# untitled_2.net
KiCad netlist of a schematic drawn in EAGLE
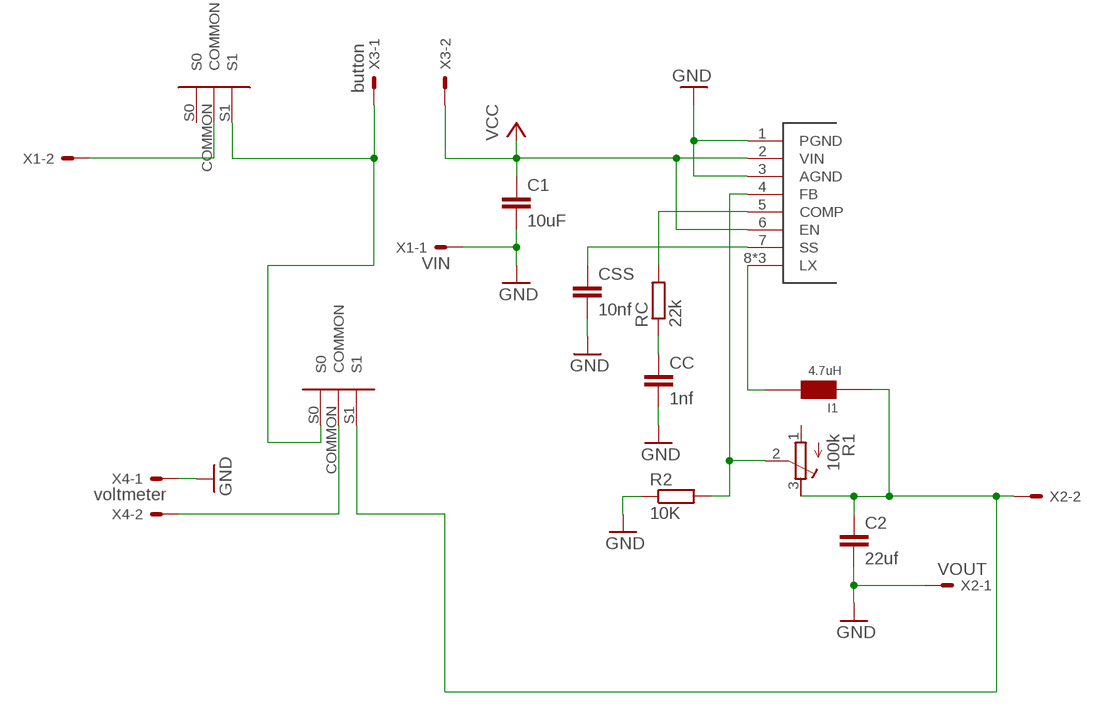
[diagram p0: schematic, sheet 1]

(export (version "E")
  (design (tool "Eeschema 10.0.6"))
  (components
    (comp (ref "C1")
      (value "10uF")
      (footprint "eagle-import:C0805K")
      (libsource (lib "eagle-import") (part "C-EUC0805K"))
    )
    (comp (ref "C2")
      (value "22uf")
      (footprint "eagle-import:C0805K")
      (libsource (lib "eagle-import") (part "C-EUC0805K"))
    )
    (comp (ref "CC")
      (value "1nf")
      (footprint "eagle-import:C1206K")
      (libsource (lib "eagle-import") (part "C-EUC1206K"))
    )
    (comp (ref "CSS")
      (value "10nf")
      (footprint "eagle-import:C1206K")
      (libsource (lib "eagle-import") (part "C-EUC1206K"))
    )
    (comp (ref "I1")
      (value "4.7uH")
      (footprint "eagle-import:RH127")
      (libsource (lib "eagle-import") (part "RH127"))
    )
    (comp (ref "MASTER_ON")
      (value "SPDT_SLIDE_SWITCH_2_PITCH")
      (footprint "eagle-import:SPDT_SLIDE_SWITCH_2_PITCH")
      (libsource (lib "eagle-import") (part "SPDT_SLIDE_SWITCH_2_PITCH"))
    )
    (comp (ref "METER_SWITCH")
      (value "SPDT_SLIDE_SWITCH_2_PITCH")
      (footprint "eagle-import:SPDT_SLIDE_SWITCH_2_PITCH")
      (libsource (lib "eagle-import") (part "SPDT_SLIDE_SWITCH_2_PITCH"))
    )
    (comp (ref "R1")
      (value "100k")
      (footprint "eagle-import:RTRIM64W")
      (libsource (lib "eagle-import") (part "R-TRIMM64W"))
    )
    (comp (ref "R2")
      (value "10K")
      (footprint "eagle-import:R1206")
      (libsource (lib "eagle-import") (part "R-EU_R1206"))
    )
    (comp (ref "RC")
      (value "22k")
      (footprint "eagle-import:R1206")
      (libsource (lib "eagle-import") (part "R-EU_R1206"))
    )
    (comp (ref "U$3")
      (value "AOZ1051PI")
      (footprint "eagle-import:AOZ1051PI")
      (libsource (lib "eagle-import") (part "AOZ1051PI"))
    )
    (comp (ref "X1")
      (value "VIN")
      (footprint "eagle-import:XH2.54")
      (fields (field (name "MF") "MOLEX") (field (name "MPN") "22-23-2021"))
      (libsource (lib "eagle-import") (part "XH2.54"))
    )
    (comp (ref "X2")
      (value "VOUT")
      (footprint "eagle-import:XH2.54")
      (fields (field (name "MF") "MOLEX") (field (name "MPN") "22-23-2021"))
      (libsource (lib "eagle-import") (part "XH2.54"))
    )
    (comp (ref "X3")
      (value "button")
      (footprint "eagle-import:XH2.54")
      (fields (field (name "MF") "MOLEX") (field (name "MPN") "22-23-2021"))
      (libsource (lib "eagle-import") (part "XH2.54"))
    )
    (comp (ref "X4")
      (value "voltmeter")
      (footprint "eagle-import:XH2.54")
      (fields (field (name "MF") "MOLEX") (field (name "MPN") "22-23-2021"))
      (libsource (lib "eagle-import") (part "XH2.54"))
    )
  )
  (nets
    (net (code "1") (name "GND") (class "Default")
      (node (ref "C1") (pin "2") (pinfunction "2_2") (pintype "passive"))
      (node (ref "C2") (pin "2") (pinfunction "2_2") (pintype "passive"))
      (node (ref "CC") (pin "2") (pinfunction "2_2") (pintype "passive"))
      (node (ref "CSS") (pin "2") (pinfunction "2_2") (pintype "passive"))
      (node (ref "R2") (pin "1") (pinfunction "1_1") (pintype "passive"))
      (node (ref "U$3") (pin "1") (pinfunction "PGND_1") (pintype "bidirectional"))
      (node (ref "U$3") (pin "3") (pinfunction "AGND_3") (pintype "bidirectional"))
      (node (ref "X1") (pin "1") (pinfunction "S_1") (pintype "passive"))
      (node (ref "X2") (pin "1") (pinfunction "S_1") (pintype "passive"))
      (node (ref "X4") (pin "1") (pinfunction "S_1") (pintype "passive"))
    )
    (net (code "2") (name "Net-(CC-Pad1)") (class "Default")
      (node (ref "CC") (pin "1") (pinfunction "1_1") (pintype "passive"))
      (node (ref "RC") (pin "1") (pinfunction "1_1") (pintype "passive"))
    )
    (net (code "3") (name "Net-(I1-PadP$1)") (class "Default")
      (node (ref "I1") (pin "P$1") (pinfunction "P$1_P$1") (pintype "bidirectional"))
      (node (ref "U$3") (pin "8") (pinfunction "LX_8") (pintype "bidirectional"))
      (node (ref "U$3") (pin "P$1") (pinfunction "LX_P$1") (pintype "bidirectional"))
      (node (ref "U$3") (pin "P$2") (pinfunction "LX_P$2") (pintype "bidirectional"))
    )
    (net (code "4") (name "Net-(R1-E)") (class "Default")
      (node (ref "C2") (pin "1") (pinfunction "1_1") (pintype "passive"))
      (node (ref "I1") (pin "P$2") (pinfunction "P$2_P$2") (pintype "bidirectional"))
      (node (ref "METER_SWITCH") (pin "S1") (pinfunction "S1_S1") (pintype "bidirectional"))
      (node (ref "R1") (pin "3") (pinfunction "E_3") (pintype "passive"))
      (node (ref "X2") (pin "2") (pinfunction "S_2") (pintype "passive"))
    )
    (net (code "5") (name "Net-(R1-S)") (class "Default")
      (node (ref "R1") (pin "2") (pinfunction "S_2") (pintype "passive"))
      (node (ref "R2") (pin "2") (pinfunction "2_2") (pintype "passive"))
      (node (ref "U$3") (pin "4") (pinfunction "FB_4") (pintype "bidirectional"))
    )
    (net (code "6") (name "Net-(U$3-COMP)") (class "Default")
      (node (ref "RC") (pin "2") (pinfunction "2_2") (pintype "passive"))
      (node (ref "U$3") (pin "5") (pinfunction "COMP_5") (pintype "bidirectional"))
    )
    (net (code "7") (name "Net-(U$3-SS)") (class "Default")
      (node (ref "CSS") (pin "1") (pinfunction "1_1") (pintype "passive"))
      (node (ref "U$3") (pin "7") (pinfunction "SS_7") (pintype "bidirectional"))
    )
    (net (code "8") (name "Net-(X1B-S)") (class "Default")
      (node (ref "MASTER_ON") (pin "COMMON") (pinfunction "COMMON_COMMON") (pintype "bidirectional"))
      (node (ref "X1") (pin "2") (pinfunction "S_2") (pintype "passive"))
    )
    (net (code "9") (name "Net-(X3A-S)") (class "Default")
      (node (ref "MASTER_ON") (pin "S1") (pinfunction "S1_S1") (pintype "bidirectional"))
      (node (ref "METER_SWITCH") (pin "S0") (pinfunction "S0_S0") (pintype "bidirectional"))
      (node (ref "X3") (pin "1") (pinfunction "S_1") (pintype "passive"))
    )
    (net (code "10") (name "Net-(X4B-S)") (class "Default")
      (node (ref "METER_SWITCH") (pin "COMMON") (pinfunction "COMMON_COMMON") (pintype "bidirectional"))
      (node (ref "X4") (pin "2") (pinfunction "S_2") (pintype "passive"))
    )
    (net (code "11") (name "VCC") (class "Default")
      (node (ref "C1") (pin "1") (pinfunction "1_1") (pintype "passive"))
      (node (ref "U$3") (pin "2") (pinfunction "VIN_2") (pintype "bidirectional"))
      (node (ref "U$3") (pin "6") (pinfunction "EN_6") (pintype "bidirectional"))
      (node (ref "X3") (pin "2") (pinfunction "S_2") (pintype "passive"))
    )
    (net (code "12") (name "unconnected-(MASTER_ON-PadS0)") (class "Default")
      (node (ref "MASTER_ON") (pin "S0") (pinfunction "S0_S0") (pintype "bidirectional"))
    )
    (net (code "13") (name "unconnected-(R1-A-Pad1)") (class "Default")
      (node (ref "R1") (pin "1") (pinfunction "A_1") (pintype "passive"))
    )
  )
)
